# ultimatedrive_2.net
KiCad netlist of a schematic drawn in EAGLE
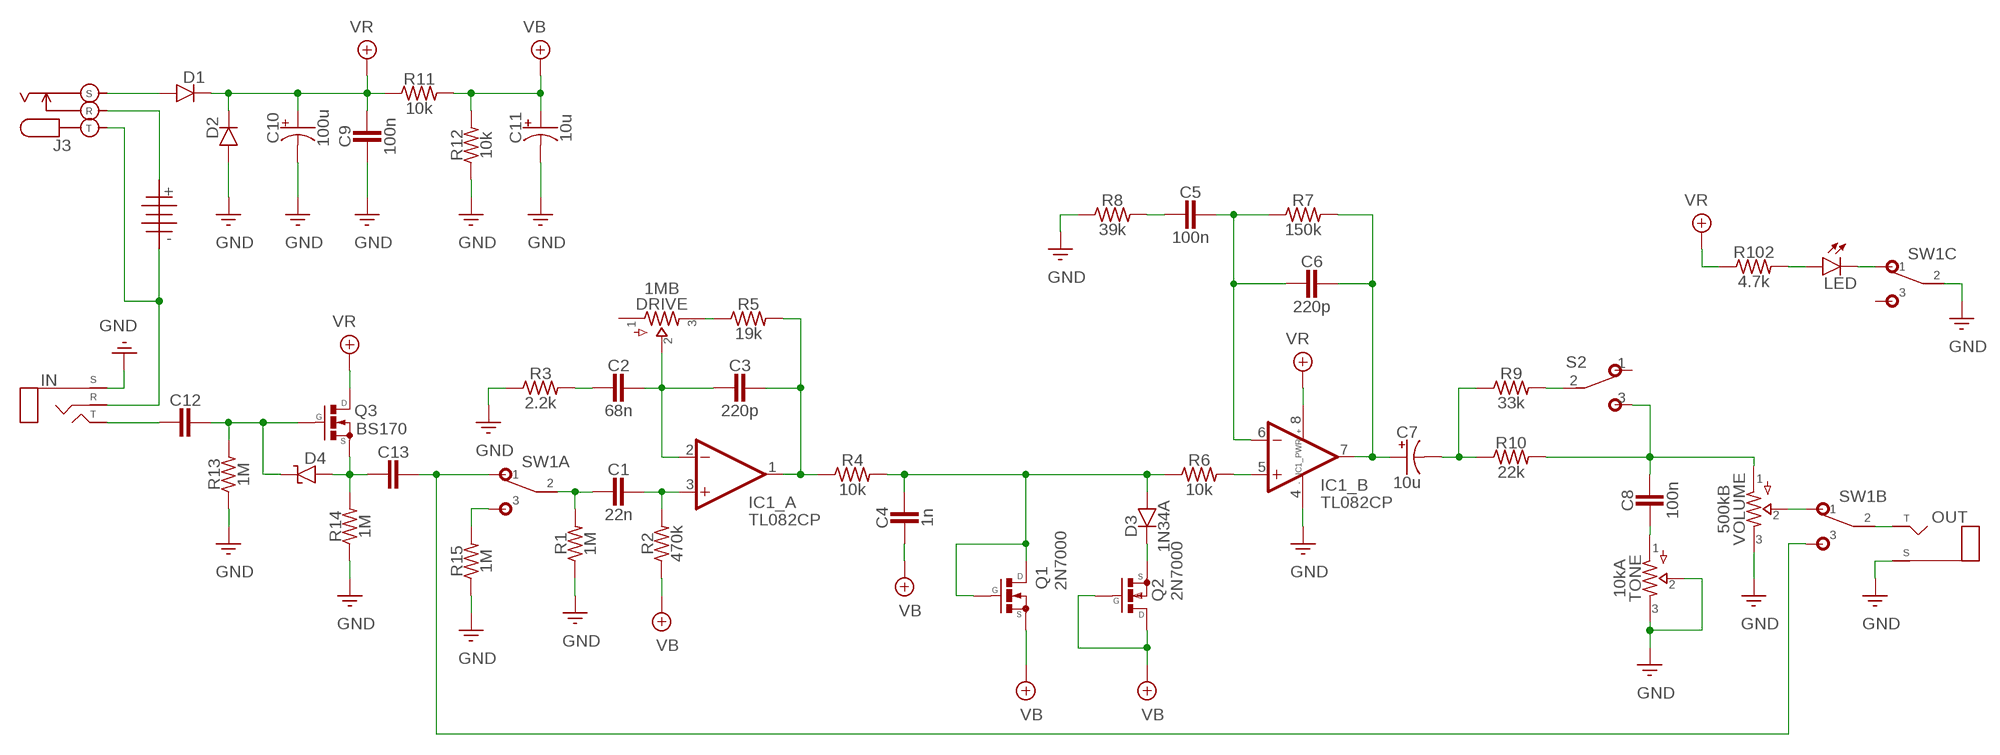
[diagram p0: schematic, sheet 1]

(export (version "E")
  (design (tool "Eeschema 10.0.6"))
  (components
    (comp (ref "1")
      (value "BATTERY")
      (footprint "eagle-import:TWO_PADS")
      (libsource (lib "eagle-import") (part "BATTERY"))
    )
    (comp (ref "C1")
      (value "22n")
      (footprint "eagle-import:BOX_SMALL")
      (libsource (lib "eagle-import") (part "CER/FILMBOX.1"))
    )
    (comp (ref "C2")
      (value "68n")
      (footprint "eagle-import:BOX_SMALL")
      (libsource (lib "eagle-import") (part "CER/FILMBOX.1"))
    )
    (comp (ref "C3")
      (value "220p")
      (footprint "eagle-import:BOX_SMALL")
      (libsource (lib "eagle-import") (part "CER/FILMBOX.1"))
    )
    (comp (ref "C4")
      (value "1n")
      (footprint "eagle-import:BOX_SMALL")
      (libsource (lib "eagle-import") (part "CER/FILMBOX.1"))
    )
    (comp (ref "C5")
      (value "100n")
      (footprint "eagle-import:BOX_SMALL")
      (libsource (lib "eagle-import") (part "CER/FILMBOX.1"))
    )
    (comp (ref "C6")
      (value "220p")
      (footprint "eagle-import:BOX_SMALL")
      (libsource (lib "eagle-import") (part "CER/FILMBOX.1"))
    )
    (comp (ref "C7")
      (value "10u")
      (footprint "eagle-import:050_020")
      (libsource (lib "eagle-import") (part "0500"))
    )
    (comp (ref "C8")
      (value "100n")
      (footprint "eagle-import:BOX_SMALL")
      (libsource (lib "eagle-import") (part "CER/FILMBOX.1"))
    )
    (comp (ref "C9")
      (value "100n")
      (footprint "eagle-import:BOX_SMALL")
      (libsource (lib "eagle-import") (part "CER/FILMBOX.1"))
    )
    (comp (ref "C10")
      (value "100u")
      (footprint "eagle-import:050_020")
      (libsource (lib "eagle-import") (part "0500"))
    )
    (comp (ref "C11")
      (value "10u")
      (footprint "eagle-import:050_020")
      (libsource (lib "eagle-import") (part "0500"))
    )
    (comp (ref "C12")
      (value "CER/FILMBOX.1")
      (footprint "eagle-import:BOX_SMALL")
      (libsource (lib "eagle-import") (part "CER/FILMBOX.1"))
    )
    (comp (ref "C13")
      (value "CER/FILMBOX.1")
      (footprint "eagle-import:BOX_SMALL")
      (libsource (lib "eagle-import") (part "CER/FILMBOX.1"))
    )
    (comp (ref "D1")
      (value "DO41.3")
      (footprint "eagle-import:DO41-3")
      (libsource (lib "eagle-import") (part "DO41.3"))
    )
    (comp (ref "D2")
      (value "DO41.3")
      (footprint "eagle-import:DO41-3")
      (libsource (lib "eagle-import") (part "DO41.3"))
    )
    (comp (ref "D3")
      (value "1N34A")
      (footprint "eagle-import:DO41-2")
      (libsource (lib "eagle-import") (part "DO41.2"))
    )
    (comp (ref "D4")
      (value "ZENER.3")
      (footprint "eagle-import:DO41-3")
      (libsource (lib "eagle-import") (part "ZENER.3"))
    )
    (comp (ref "DRIVE")
      (value "1MB")
      (footprint "eagle-import:16MM")
      (libsource (lib "eagle-import") (part "POTS16MM"))
    )
    (comp (ref "IC1")
      (value "TL082CP")
      (footprint "eagle-import:DIL0")
      (libsource (lib "eagle-import") (part "DUALTH"))
    )
    (comp (ref "IN")
      (value "STEREO")
      (footprint "eagle-import:STEREO_PCB")
      (libsource (lib "eagle-import") (part "STEREO"))
    )
    (comp (ref "J3")
      (value "DC_KOBICONN")
      (footprint "eagle-import:DC_KOBICONN")
      (libsource (lib "eagle-import") (part "DC_KOBICONN"))
    )
    (comp (ref "LED")
      (value "LED")
      (footprint "eagle-import:3MM_D")
      (libsource (lib "eagle-import") (part "LED"))
    )
    (comp (ref "OUT")
      (value "MONO")
      (footprint "eagle-import:TWO_PADS")
      (libsource (lib "eagle-import") (part "MONO"))
    )
    (comp (ref "Q1")
      (value "2N7000")
      (footprint "eagle-import:TO92-")
      (libsource (lib "eagle-import") (part "2N7000"))
    )
    (comp (ref "Q2")
      (value "2N7000")
      (footprint "eagle-import:TO92-")
      (libsource (lib "eagle-import") (part "2N7000"))
    )
    (comp (ref "Q3")
      (value "BS170")
      (footprint "eagle-import:SOT54ES")
      (libsource (lib "eagle-import") (part "BS170"))
    )
    (comp (ref "R1")
      (value "1M")
      (footprint "eagle-import:R0207_3")
      (libsource (lib "eagle-import") (part "R_.3B"))
    )
    (comp (ref "R2")
      (value "470k")
      (footprint "eagle-import:R0207_3")
      (libsource (lib "eagle-import") (part "R_.3B"))
    )
    (comp (ref "R3")
      (value "2.2k")
      (footprint "eagle-import:R0207_3")
      (libsource (lib "eagle-import") (part "R_.3B"))
    )
    (comp (ref "R4")
      (value "10k")
      (footprint "eagle-import:R0207_3")
      (libsource (lib "eagle-import") (part "R_.3B"))
    )
    (comp (ref "R5")
      (value "19k")
      (footprint "eagle-import:R0207_3")
      (libsource (lib "eagle-import") (part "R_.3B"))
    )
    (comp (ref "R6")
      (value "10k")
      (footprint "eagle-import:R0207_3")
      (libsource (lib "eagle-import") (part "R_.3B"))
    )
    (comp (ref "R7")
      (value "150k")
      (footprint "eagle-import:R0207_3")
      (libsource (lib "eagle-import") (part "R_.3B"))
    )
    (comp (ref "R8")
      (value "39k")
      (footprint "eagle-import:R0207_3")
      (libsource (lib "eagle-import") (part "R_.3B"))
    )
    (comp (ref "R9")
      (value "33k")
      (footprint "eagle-import:R0207_3")
      (libsource (lib "eagle-import") (part "R_.3B"))
    )
    (comp (ref "R10")
      (value "22k")
      (footprint "eagle-import:R0207_3")
      (libsource (lib "eagle-import") (part "R_.3B"))
    )
    (comp (ref "R11")
      (value "10k")
      (footprint "eagle-import:R0207_3")
      (libsource (lib "eagle-import") (part "R_.3B"))
    )
    (comp (ref "R12")
      (value "10k")
      (footprint "eagle-import:R0207_3")
      (libsource (lib "eagle-import") (part "R_.3B"))
    )
    (comp (ref "R13")
      (value "1M")
      (footprint "eagle-import:R0207_3")
      (libsource (lib "eagle-import") (part "R_.3B"))
    )
    (comp (ref "R14")
      (value "1M")
      (footprint "eagle-import:R0207_3")
      (libsource (lib "eagle-import") (part "R_.3B"))
    )
    (comp (ref "R15")
      (value "1M")
      (footprint "eagle-import:R0207_3")
      (libsource (lib "eagle-import") (part "R_.3B"))
    )
    (comp (ref "R102")
      (value "4.7k")
      (footprint "eagle-import:R0207_3")
      (libsource (lib "eagle-import") (part "R_.3B"))
    )
    (comp (ref "S2")
      (value "SPDT")
      (footprint "eagle-import:M9040P")
      (libsource (lib "eagle-import") (part "SPDT"))
    )
    (comp (ref "SW1")
      (value "3PDT")
      (footprint "eagle-import:3PDT")
      (libsource (lib "eagle-import") (part "3PDT"))
    )
    (comp (ref "TONE")
      (value "10kA")
      (footprint "eagle-import:16MM")
      (libsource (lib "eagle-import") (part "POTS16MM"))
    )
    (comp (ref "VOLUME")
      (value "500kB")
      (footprint "eagle-import:16MM")
      (libsource (lib "eagle-import") (part "POTS16MM"))
    )
  )
  (nets
    (net (code "1") (name "GND") (class "Default")
      (node (ref "C10") (pin "-") (pinfunction "-_-") (pintype "passive"))
      (node (ref "C11") (pin "-") (pinfunction "-_-") (pintype "passive"))
      (node (ref "C9") (pin "2") (pinfunction "2_2") (pintype "passive"))
      (node (ref "D2") (pin "A") (pinfunction "A_A") (pintype "passive"))
      (node (ref "IC1") (pin "4") (pinfunction "V-_4") (pintype "power_in"))
      (node (ref "IN") (pin "P$1") (pinfunction "S_P$1") (pintype "passive"))
      (node (ref "OUT") (pin "S") (pinfunction "SLEEVE_S") (pintype "passive"))
      (node (ref "R1") (pin "1") (pinfunction "1_1") (pintype "passive"))
      (node (ref "R12") (pin "1") (pinfunction "1_1") (pintype "passive"))
      (node (ref "R13") (pin "1") (pinfunction "1_1") (pintype "passive"))
      (node (ref "R14") (pin "1") (pinfunction "1_1") (pintype "passive"))
      (node (ref "R15") (pin "1") (pinfunction "1_1") (pintype "passive"))
      (node (ref "R3") (pin "1") (pinfunction "1_1") (pintype "passive"))
      (node (ref "R8") (pin "1") (pinfunction "1_1") (pintype "passive"))
      (node (ref "SW1") (pin "C2") (pinfunction "2_C2") (pintype "passive"))
      (node (ref "TONE") (pin "2") (pinfunction "2_2") (pintype "passive"))
      (node (ref "TONE") (pin "3") (pinfunction "3_3") (pintype "passive"))
      (node (ref "VOLUME") (pin "3") (pinfunction "3_3") (pintype "passive"))
    )
    (net (code "2") (name "Net-(1-P$1)") (class "Default")
      (node (ref "1") (pin "T") (pinfunction "P$1_T") (pintype "bidirectional"))
      (node (ref "J3") (pin "R") (pinfunction "R_R") (pintype "bidirectional"))
    )
    (net (code "3") (name "Net-(1-P$2)") (class "Default")
      (node (ref "1") (pin "S") (pinfunction "P$2_S") (pintype "bidirectional"))
      (node (ref "IN") (pin "P$2") (pinfunction "R_P$2") (pintype "passive"))
      (node (ref "J3") (pin "T") (pinfunction "T_T") (pintype "bidirectional"))
    )
    (net (code "4") (name "Net-(C2-Pad2)") (class "Default")
      (node (ref "C2") (pin "2") (pinfunction "2_2") (pintype "passive"))
      (node (ref "R3") (pin "2") (pinfunction "2_2") (pintype "passive"))
    )
    (net (code "5") (name "Net-(C5-Pad2)") (class "Default")
      (node (ref "C5") (pin "2") (pinfunction "2_2") (pintype "passive"))
      (node (ref "R8") (pin "2") (pinfunction "2_2") (pintype "passive"))
    )
    (net (code "6") (name "Net-(C7-Pad-)") (class "Default")
      (node (ref "C7") (pin "-") (pinfunction "-_-") (pintype "passive"))
      (node (ref "R10") (pin "1") (pinfunction "1_1") (pintype "passive"))
      (node (ref "R9") (pin "1") (pinfunction "1_1") (pintype "passive"))
    )
    (net (code "7") (name "Net-(C8-Pad2)") (class "Default")
      (node (ref "C8") (pin "2") (pinfunction "2_2") (pintype "passive"))
      (node (ref "TONE") (pin "1") (pinfunction "1_1") (pintype "passive"))
    )
    (net (code "8") (name "Net-(C12-Pad1)") (class "Default")
      (node (ref "C12") (pin "1") (pinfunction "1_1") (pintype "passive"))
      (node (ref "D4") (pin "C") (pinfunction "C_C") (pintype "passive"))
      (node (ref "Q3") (pin "G") (pinfunction "G_G") (pintype "passive"))
      (node (ref "R13") (pin "2") (pinfunction "2_2") (pintype "passive"))
    )
    (net (code "9") (name "Net-(C13-Pad2)") (class "Default")
      (node (ref "C13") (pin "2") (pinfunction "2_2") (pintype "passive"))
      (node (ref "D4") (pin "A") (pinfunction "A_A") (pintype "passive"))
      (node (ref "Q3") (pin "S") (pinfunction "S_S") (pintype "passive"))
      (node (ref "R14") (pin "2") (pinfunction "2_2") (pintype "passive"))
    )
    (net (code "10") (name "Net-(D1-PadA)") (class "Default")
      (node (ref "D1") (pin "A") (pinfunction "A_A") (pintype "passive"))
      (node (ref "J3") (pin "S") (pinfunction "S_S") (pintype "bidirectional"))
    )
    (net (code "11") (name "Net-(DRIVE-Pad3)") (class "Default")
      (node (ref "DRIVE") (pin "3") (pinfunction "3_3") (pintype "passive"))
      (node (ref "R5") (pin "1") (pinfunction "1_1") (pintype "passive"))
    )
    (net (code "12") (name "Net-(IC1A-+IN)") (class "Default")
      (node (ref "C1") (pin "1") (pinfunction "1_1") (pintype "passive"))
      (node (ref "IC1") (pin "3") (pinfunction "+IN_3") (pintype "input"))
      (node (ref "R2") (pin "2") (pinfunction "2_2") (pintype "passive"))
    )
    (net (code "13") (name "Net-(IC1A--IN)") (class "Default")
      (node (ref "C2") (pin "1") (pinfunction "1_1") (pintype "passive"))
      (node (ref "C3") (pin "2") (pinfunction "2_2") (pintype "passive"))
      (node (ref "DRIVE") (pin "2") (pinfunction "2_2") (pintype "passive"))
      (node (ref "IC1") (pin "2") (pinfunction "-IN_2") (pintype "input"))
    )
    (net (code "14") (name "Net-(IC1A-OUT)") (class "Default")
      (node (ref "C3") (pin "1") (pinfunction "1_1") (pintype "passive"))
      (node (ref "IC1") (pin "1") (pinfunction "OUT_1") (pintype "output"))
      (node (ref "R4") (pin "1") (pinfunction "1_1") (pintype "passive"))
      (node (ref "R5") (pin "2") (pinfunction "2_2") (pintype "passive"))
    )
    (net (code "15") (name "Net-(IC1B-+IN)") (class "Default")
      (node (ref "IC1") (pin "5") (pinfunction "+IN_5") (pintype "input"))
      (node (ref "R6") (pin "2") (pinfunction "2_2") (pintype "passive"))
    )
    (net (code "16") (name "Net-(IC1B--IN)") (class "Default")
      (node (ref "C5") (pin "1") (pinfunction "1_1") (pintype "passive"))
      (node (ref "C6") (pin "2") (pinfunction "2_2") (pintype "passive"))
      (node (ref "IC1") (pin "6") (pinfunction "-IN_6") (pintype "input"))
      (node (ref "R7") (pin "1") (pinfunction "1_1") (pintype "passive"))
    )
    (net (code "17") (name "Net-(IC1B-OUT)") (class "Default")
      (node (ref "C6") (pin "1") (pinfunction "1_1") (pintype "passive"))
      (node (ref "C7") (pin "+") (pinfunction "+_+") (pintype "passive"))
      (node (ref "IC1") (pin "7") (pinfunction "OUT_7") (pintype "output"))
      (node (ref "R7") (pin "2") (pinfunction "2_2") (pintype "passive"))
    )
    (net (code "18") (name "Net-(IN-T)") (class "Default")
      (node (ref "C12") (pin "2") (pinfunction "2_2") (pintype "passive"))
      (node (ref "IN") (pin "P$3") (pinfunction "T_P$3") (pintype "passive"))
    )
    (net (code "19") (name "Net-(LED-A)") (class "Default")
      (node (ref "LED") (pin "ANODE") (pinfunction "A_ANODE") (pintype "passive"))
      (node (ref "R102") (pin "2") (pinfunction "2_2") (pintype "passive"))
    )
    (net (code "20") (name "Net-(LED-C)") (class "Default")
      (node (ref "LED") (pin "P$1") (pinfunction "C_P$1") (pintype "passive"))
      (node (ref "SW1") (pin "C1") (pinfunction "1_C1") (pintype "passive"))
    )
    (net (code "21") (name "Net-(OUT-TIP)") (class "Default")
      (node (ref "OUT") (pin "T") (pinfunction "TIP_T") (pintype "passive"))
      (node (ref "SW1") (pin "B2") (pinfunction "2_B2") (pintype "passive"))
    )
    (net (code "22") (name "Net-(Q1-D)") (class "Default")
      (node (ref "C4") (pin "1") (pinfunction "1_1") (pintype "passive"))
      (node (ref "D3") (pin "A") (pinfunction "A_A") (pintype "passive"))
      (node (ref "Q1") (pin "1") (pinfunction "D_1") (pintype "passive"))
      (node (ref "Q1") (pin "2") (pinfunction "G_2") (pintype "passive"))
      (node (ref "R4") (pin "2") (pinfunction "2_2") (pintype "passive"))
      (node (ref "R6") (pin "1") (pinfunction "1_1") (pintype "passive"))
    )
    (net (code "23") (name "Net-(Q2-S)") (class "Default")
      (node (ref "D3") (pin "C") (pinfunction "C_C") (pintype "passive"))
      (node (ref "Q2") (pin "3") (pinfunction "S_3") (pintype "passive"))
    )
    (net (code "24") (name "Net-(S2-P)") (class "Default")
      (node (ref "R9") (pin "2") (pinfunction "2_2") (pintype "passive"))
      (node (ref "S2") (pin "2") (pinfunction "P_2") (pintype "passive"))
    )
    (net (code "25") (name "Net-(S2-S)") (class "Default")
      (node (ref "C8") (pin "1") (pinfunction "1_1") (pintype "passive"))
      (node (ref "R10") (pin "2") (pinfunction "2_2") (pintype "passive"))
      (node (ref "S2") (pin "3") (pinfunction "S_3") (pintype "passive"))
      (node (ref "VOLUME") (pin "1") (pinfunction "1_1") (pintype "passive"))
    )
    (net (code "26") (name "Net-(SW1A-1)") (class "Default")
      (node (ref "C13") (pin "1") (pinfunction "1_1") (pintype "passive"))
      (node (ref "SW1") (pin "A1") (pinfunction "1_A1") (pintype "passive"))
      (node (ref "SW1") (pin "B3") (pinfunction "3_B3") (pintype "passive"))
    )
    (net (code "27") (name "Net-(SW1A-2)") (class "Default")
      (node (ref "C1") (pin "2") (pinfunction "2_2") (pintype "passive"))
      (node (ref "R1") (pin "2") (pinfunction "2_2") (pintype "passive"))
      (node (ref "SW1") (pin "A2") (pinfunction "2_A2") (pintype "passive"))
    )
    (net (code "28") (name "Net-(SW1A-3)") (class "Default")
      (node (ref "R15") (pin "2") (pinfunction "2_2") (pintype "passive"))
      (node (ref "SW1") (pin "A3") (pinfunction "3_A3") (pintype "passive"))
    )
    (net (code "29") (name "Net-(SW1B-1)") (class "Default")
      (node (ref "SW1") (pin "B1") (pinfunction "1_B1") (pintype "passive"))
      (node (ref "VOLUME") (pin "2") (pinfunction "2_2") (pintype "passive"))
    )
    (net (code "30") (name "VB") (class "Default")
      (node (ref "C11") (pin "+") (pinfunction "+_+") (pintype "passive"))
      (node (ref "C4") (pin "2") (pinfunction "2_2") (pintype "passive"))
      (node (ref "Q1") (pin "3") (pinfunction "S_3") (pintype "passive"))
      (node (ref "Q2") (pin "1") (pinfunction "D_1") (pintype "passive"))
      (node (ref "Q2") (pin "2") (pinfunction "G_2") (pintype "passive"))
      (node (ref "R11") (pin "2") (pinfunction "2_2") (pintype "passive"))
      (node (ref "R12") (pin "2") (pinfunction "2_2") (pintype "passive"))
      (node (ref "R2") (pin "1") (pinfunction "1_1") (pintype "passive"))
    )
    (net (code "31") (name "VR") (class "Default")
      (node (ref "C10") (pin "+") (pinfunction "+_+") (pintype "passive"))
      (node (ref "C9") (pin "1") (pinfunction "1_1") (pintype "passive"))
      (node (ref "D1") (pin "C") (pinfunction "C_C") (pintype "passive"))
      (node (ref "D2") (pin "C") (pinfunction "C_C") (pintype "passive"))
      (node (ref "IC1") (pin "8") (pinfunction "V+_8") (pintype "power_in"))
      (node (ref "Q3") (pin "D") (pinfunction "D_D") (pintype "passive"))
      (node (ref "R102") (pin "1") (pinfunction "1_1") (pintype "passive"))
      (node (ref "R11") (pin "1") (pinfunction "1_1") (pintype "passive"))
    )
    (net (code "32") (name "unconnected-(DRIVE-Pad1)") (class "Default")
      (node (ref "DRIVE") (pin "1") (pinfunction "1_1") (pintype "passive"))
    )
    (net (code "33") (name "unconnected-(S2-O-Pad1)") (class "Default")
      (node (ref "S2") (pin "1") (pinfunction "O_1") (pintype "passive"))
    )
    (net (code "34") (name "unconnected-(SW1C-3-PadC3)") (class "Default")
      (node (ref "SW1") (pin "C3") (pinfunction "3_C3") (pintype "passive"))
    )
  )
)
